# Battery_Connection.net
KiCad netlist of a schematic drawn in Altium Designer
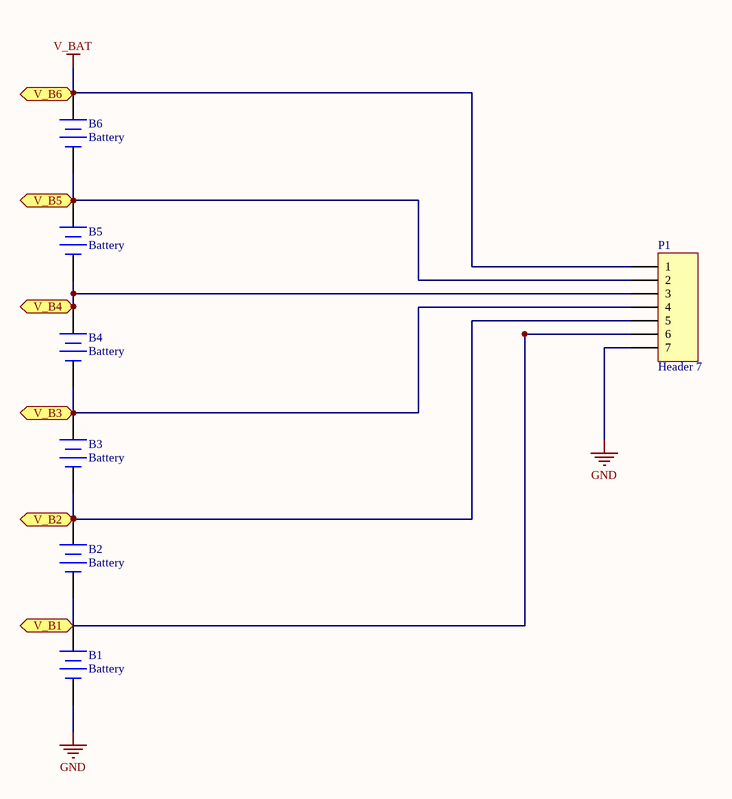
[diagram p0: Battery Connection.SchDoc]

(export (version "E")
  (design (tool "Eeschema 10.0.6"))
  (components
    (comp (ref "B1")
      (value "Battery")
      (footprint "BAT-2")
      (description "Multicell Battery")
      (fields (field (name "PUBLISHER") "Altium Limited"))
      (libsource (lib "Miscellaneous Devices") (part "Battery"))
    )
    (comp (ref "B2")
      (value "Battery")
      (footprint "BAT-2")
      (description "Multicell Battery")
      (fields (field (name "PUBLISHER") "Altium Limited"))
      (libsource (lib "Miscellaneous Devices") (part "Battery"))
    )
    (comp (ref "B3")
      (value "Battery")
      (footprint "BAT-2")
      (description "Multicell Battery")
      (fields (field (name "PUBLISHER") "Altium Limited"))
      (libsource (lib "Miscellaneous Devices") (part "Battery"))
    )
    (comp (ref "B4")
      (value "Battery")
      (footprint "BAT-2")
      (description "Multicell Battery")
      (fields (field (name "PUBLISHER") "Altium Limited"))
      (libsource (lib "Miscellaneous Devices") (part "Battery"))
    )
    (comp (ref "B5")
      (value "Battery")
      (footprint "BAT-2")
      (description "Multicell Battery")
      (fields (field (name "PUBLISHER") "Altium Limited"))
      (libsource (lib "Miscellaneous Devices") (part "Battery"))
    )
    (comp (ref "B6")
      (value "Battery")
      (footprint "BAT-2")
      (description "Multicell Battery")
      (fields (field (name "PUBLISHER") "Altium Limited"))
      (libsource (lib "Miscellaneous Devices") (part "Battery"))
    )
    (comp (ref "P1")
      (value "Header 7")
      (footprint "HDR1X7")
      (description "Header, 7-Pin")
      (fields (field (name "PUBLISHER") "Altium Limited"))
      (libsource (lib "Miscellaneous Connectors") (part "Header 7"))
    )
  )
  (nets
    (net (code "1") (name "/V_B1") (class "Default")
      (node (ref "P1") (pin "6") (pinfunction "6_6") (pintype "passive"))
    )
    (net (code "2") (name "/V_B2") (class "Default")
      (node (ref "B2") (pin "1") (pinfunction "+_1") (pintype "passive"))
      (node (ref "B3") (pin "2") (pinfunction "-_2") (pintype "passive"))
      (node (ref "P1") (pin "5") (pinfunction "5_5") (pintype "passive"))
    )
    (net (code "3") (name "/V_B3") (class "Default")
      (node (ref "B3") (pin "1") (pinfunction "+_1") (pintype "passive"))
      (node (ref "B4") (pin "2") (pinfunction "-_2") (pintype "passive"))
      (node (ref "P1") (pin "4") (pinfunction "4_4") (pintype "passive"))
    )
    (net (code "4") (name "/V_B4") (class "Default")
      (node (ref "B4") (pin "1") (pinfunction "+_1") (pintype "passive"))
      (node (ref "B5") (pin "2") (pinfunction "-_2") (pintype "passive"))
      (node (ref "P1") (pin "3") (pinfunction "3_3") (pintype "passive"))
    )
    (net (code "5") (name "/V_B5") (class "Default")
      (node (ref "B5") (pin "1") (pinfunction "+_1") (pintype "passive"))
      (node (ref "B6") (pin "2") (pinfunction "-_2") (pintype "passive"))
      (node (ref "P1") (pin "2") (pinfunction "2_2") (pintype "passive"))
    )
    (net (code "7") (name "GND") (class "Default")
      (node (ref "B1") (pin "2") (pinfunction "-_2") (pintype "passive"))
      (node (ref "P1") (pin "7") (pinfunction "7_7") (pintype "passive"))
    )
    (net (code "8") (name "Net-(B1-+)") (class "Default")
      (node (ref "B1") (pin "1") (pinfunction "+_1") (pintype "passive"))
      (node (ref "B2") (pin "2") (pinfunction "-_2") (pintype "passive"))
    )
    (net (code "9") (name "V_BAT") (class "Default")
      (node (ref "B6") (pin "1") (pinfunction "+_1") (pintype "passive"))
      (node (ref "P1") (pin "1") (pinfunction "1_1") (pintype "passive"))
    )
  )
)
